# MCU.net
KiCad netlist of a schematic drawn in Altium Designer
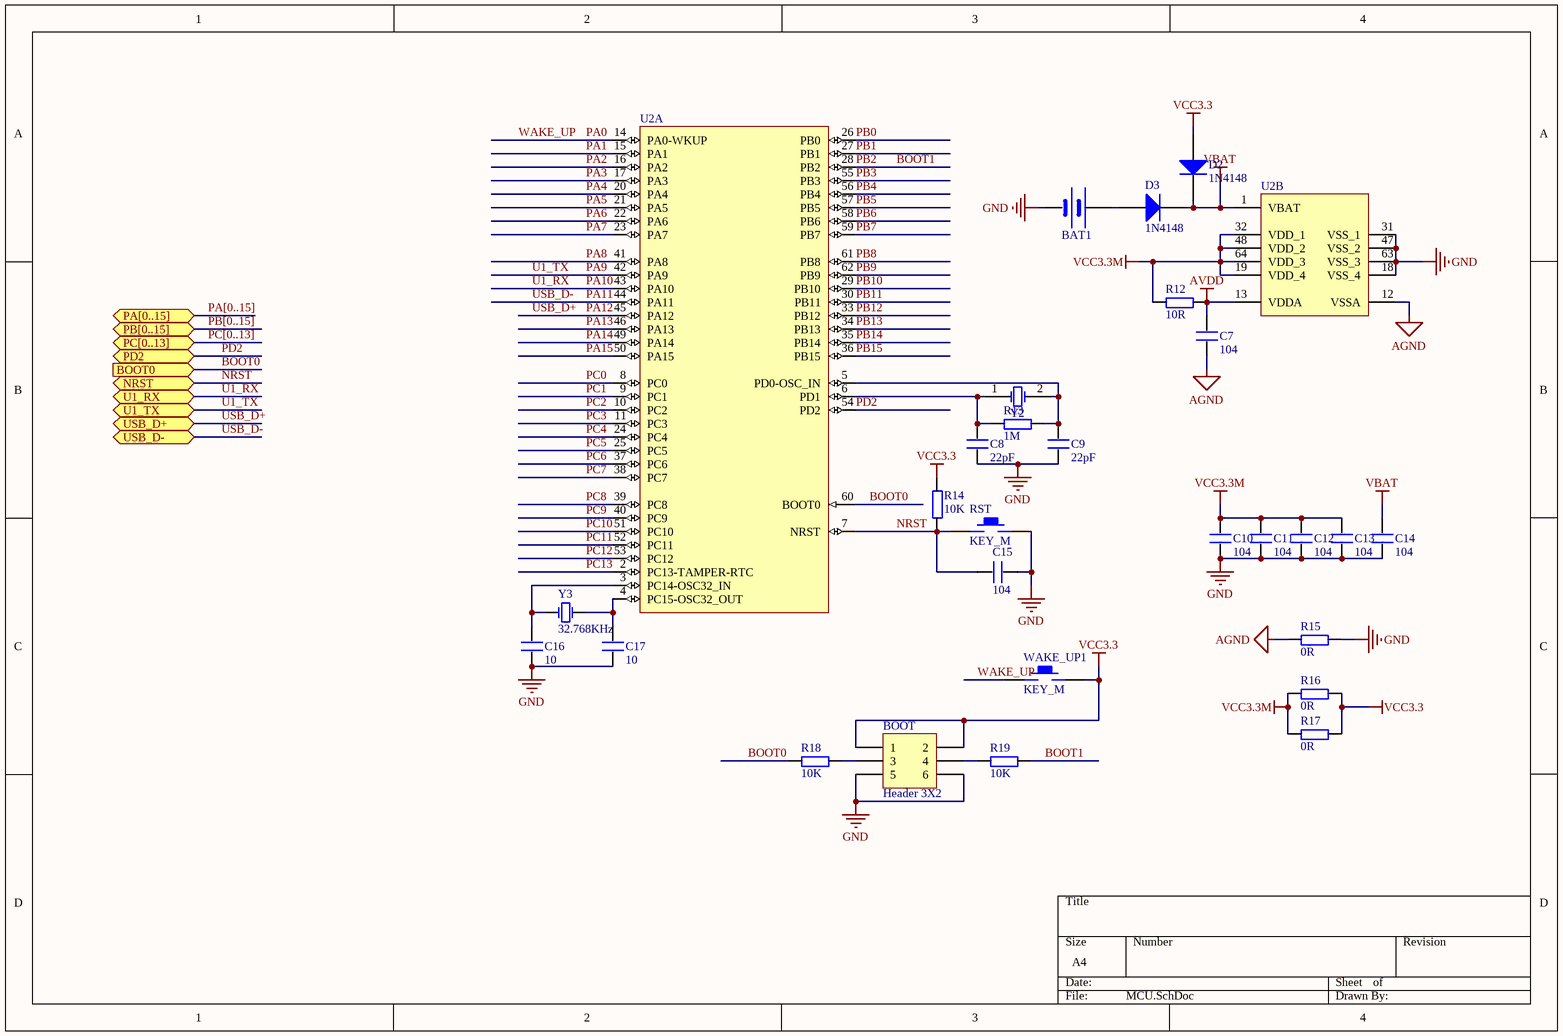
[diagram p0: MCU.SchDoc]

(export (version "E")
  (design (tool "Eeschema 10.0.6"))
  (components
    (comp (ref "BAT1")
      (value "BATT")
      (footprint "CR1220_B")
      (libsource (lib "WarShip V3 STM32103封装库") (part "BAT"))
    )
    (comp (ref "BOOT")
      (value "Header 3X2")
      (footprint "HDR2X3")
      (description "Header, 3-Pin, Dual row")
      (fields (field (name "PUBLISHER") "Altium Limited"))
      (libsource (lib "Miscellaneous Connectors") (part "Header 3X2"))
    )
    (comp (ref "C7") (value "104") (footprint "0603C") (libsource (lib "WarShip V3 STM32103封装库") (part "C")))
    (comp (ref "C8") (value "22pF") (footprint "0603C") (libsource (lib "WarShip V3 STM32103封装库") (part "C")))
    (comp (ref "C9") (value "22pF") (footprint "0603C") (libsource (lib "WarShip V3 STM32103封装库") (part "C")))
    (comp (ref "C10") (value "104") (footprint "0603C") (libsource (lib "WarShip V3 STM32103封装库") (part "C")))
    (comp (ref "C11") (value "104") (footprint "0603C") (libsource (lib "WarShip V3 STM32103封装库") (part "C")))
    (comp (ref "C12") (value "104") (footprint "0603C") (libsource (lib "WarShip V3 STM32103封装库") (part "C")))
    (comp (ref "C13") (value "104") (footprint "0603C") (libsource (lib "WarShip V3 STM32103封装库") (part "C")))
    (comp (ref "C14") (value "104") (footprint "0603C") (libsource (lib "WarShip V3 STM32103封装库") (part "C")))
    (comp (ref "C15") (value "104") (footprint "0603C") (libsource (lib "STM32F429核心板封装库") (part "C")))
    (comp (ref "C16") (value "10") (footprint "0603C") (libsource (lib "WarShip V3 STM32103封装库") (part "C")))
    (comp (ref "C17") (value "10") (footprint "0603C") (libsource (lib "WarShip V3 STM32103封装库") (part "C")))
    (comp (ref "D2")
      (value "1N4148")
      (footprint "DIODE_SOP")
      (description "Default Diode")
      (fields (field (name "PUBLISHER") "Altium Limited"))
      (libsource (lib "3D库") (part "Diode"))
    )
    (comp (ref "D3")
      (value "1N4148")
      (footprint "DIODE_SOP")
      (description "Default Diode")
      (fields (field (name "PUBLISHER") "Altium Limited"))
      (libsource (lib "3D库") (part "Diode"))
    )
    (comp (ref "R12") (value "10R") (footprint "0603R") (libsource (lib "WarShip V3 STM32103封装库") (part "R")))
    (comp (ref "R13") (value "1M") (footprint "0603R") (libsource (lib "Explorer STM32F407封装库") (part "R")))
    (comp (ref "R14") (value "10K") (footprint "0603R") (libsource (lib "STM32F429核心板封装库") (part "R")))
    (comp (ref "R15") (value "0R") (footprint "0603R") (libsource (lib "WarShip V3 STM32103封装库") (part "R")))
    (comp (ref "R16") (value "0R") (footprint "0603R") (libsource (lib "STM32F429核心板封装库") (part "R")))
    (comp (ref "R17") (value "0R") (footprint "0603R") (libsource (lib "STM32F429核心板封装库") (part "R")))
    (comp (ref "R18") (value "10K") (footprint "0603R") (libsource (lib "Explorer STM32F407封装库") (part "R")))
    (comp (ref "R19") (value "10K") (footprint "0603R") (libsource (lib "Explorer STM32F407封装库") (part "R")))
    (comp (ref "RST")
      (value "KEY_M")
      (footprint "KEY_SOP3625_B")
      (libsource (lib "STM32F429核心板封装库") (part "KEY_M"))
    )
    (comp (ref "U2")
      (value "~")
      (footprint "LQFP64-10x10mm")
      (libsource (lib "STMicroelectronics STM32 F1") (part "STM32F103RCT6"))
    )
    (comp (ref "WAKE_UP1")
      (value "KEY_M")
      (footprint "KEY_SOP3625_B")
      (libsource (lib "STM32F429核心板封装库") (part "KEY_M"))
    )
    (comp (ref "Y2")
      (value "NX3225GD-8.000M-EXS00A-CG04874[N/A]")
      (footprint "XTAL_SMD")
      (description "Crystal Oscillator")
      (fields (field (name "PUBLISHER") "Altium Limited"))
      (libsource (lib "3D库") (part "XTAL"))
    )
    (comp (ref "Y3")
      (value "32.768KHz")
      (footprint "XTAL_2SM_3R2X1R5")
      (description "普通晶振")
      (fields (field (name "PUBLISHER") "Altium Limited"))
      (libsource (lib "STM32F429核心板封装库") (part "XTAL"))
    )
  )
  (nets
    (net (code "1") (name "/BOOT0") (class "Default")
      (node (ref "R18") (pin "1") (pintype "passive"))
      (node (ref "U2") (pin "60") (pinfunction "BOOT0_60") (pintype "input"))
    )
    (net (code "2") (name "/NRST") (class "Default")
      (node (ref "C15") (pin "1") (pintype "passive"))
      (node (ref "R14") (pin "1") (pintype "passive"))
      (node (ref "RST") (pin "1") (pinfunction "1_1") (pintype "passive"))
      (node (ref "U2") (pin "7") (pinfunction "NRST_7") (pintype "bidirectional"))
    )
    (net (code "3") (name "/PA0") (class "Default")
      (node (ref "U2") (pin "14") (pinfunction "PA0-WKUP_14") (pintype "bidirectional"))
      (node (ref "WAKE_UP1") (pin "1") (pinfunction "1_1") (pintype "passive"))
    )
    (net (code "4") (name "/PA1") (class "Default")
      (node (ref "U2") (pin "15") (pinfunction "PA1_15") (pintype "bidirectional"))
    )
    (net (code "5") (name "/PA2") (class "Default")
      (node (ref "U2") (pin "16") (pinfunction "PA2_16") (pintype "bidirectional"))
    )
    (net (code "6") (name "/PA3") (class "Default")
      (node (ref "U2") (pin "17") (pinfunction "PA3_17") (pintype "bidirectional"))
    )
    (net (code "7") (name "/PA4") (class "Default")
      (node (ref "U2") (pin "20") (pinfunction "PA4_20") (pintype "bidirectional"))
    )
    (net (code "8") (name "/PA5") (class "Default")
      (node (ref "U2") (pin "21") (pinfunction "PA5_21") (pintype "bidirectional"))
    )
    (net (code "9") (name "/PA6") (class "Default")
      (node (ref "U2") (pin "22") (pinfunction "PA6_22") (pintype "bidirectional"))
    )
    (net (code "10") (name "/PA7") (class "Default")
      (node (ref "U2") (pin "23") (pinfunction "PA7_23") (pintype "bidirectional"))
    )
    (net (code "11") (name "/PA8") (class "Default")
      (node (ref "U2") (pin "41") (pinfunction "PA8_41") (pintype "bidirectional"))
    )
    (net (code "12") (name "/PA9") (class "Default")
      (node (ref "U2") (pin "42") (pinfunction "PA9_42") (pintype "bidirectional"))
    )
    (net (code "13") (name "/PA10") (class "Default")
      (node (ref "U2") (pin "43") (pinfunction "PA10_43") (pintype "bidirectional"))
    )
    (net (code "14") (name "/PA11") (class "Default")
      (node (ref "U2") (pin "44") (pinfunction "PA11_44") (pintype "bidirectional"))
    )
    (net (code "15") (name "/PA12") (class "Default")
      (node (ref "U2") (pin "45") (pinfunction "PA12_45") (pintype "bidirectional"))
    )
    (net (code "16") (name "/PA13") (class "Default")
      (node (ref "U2") (pin "46") (pinfunction "PA13_46") (pintype "bidirectional"))
    )
    (net (code "17") (name "/PA14") (class "Default")
      (node (ref "U2") (pin "49") (pinfunction "PA14_49") (pintype "bidirectional"))
    )
    (net (code "18") (name "/PA15") (class "Default")
      (node (ref "U2") (pin "50") (pinfunction "PA15_50") (pintype "bidirectional"))
    )
    (net (code "20") (name "/PB0") (class "Default")
      (node (ref "U2") (pin "26") (pinfunction "PB0_26") (pintype "bidirectional"))
    )
    (net (code "21") (name "/PB1") (class "Default")
      (node (ref "U2") (pin "27") (pinfunction "PB1_27") (pintype "bidirectional"))
    )
    (net (code "22") (name "/PB2") (class "Default")
      (node (ref "R19") (pin "2") (pintype "passive"))
      (node (ref "U2") (pin "28") (pinfunction "PB2_28") (pintype "bidirectional"))
    )
    (net (code "23") (name "/PB3") (class "Default")
      (node (ref "U2") (pin "55") (pinfunction "PB3_55") (pintype "bidirectional"))
    )
    (net (code "24") (name "/PB4") (class "Default")
      (node (ref "U2") (pin "56") (pinfunction "PB4_56") (pintype "bidirectional"))
    )
    (net (code "25") (name "/PB5") (class "Default")
      (node (ref "U2") (pin "57") (pinfunction "PB5_57") (pintype "bidirectional"))
    )
    (net (code "26") (name "/PB6") (class "Default")
      (node (ref "U2") (pin "58") (pinfunction "PB6_58") (pintype "bidirectional"))
    )
    (net (code "27") (name "/PB7") (class "Default")
      (node (ref "U2") (pin "59") (pinfunction "PB7_59") (pintype "bidirectional"))
    )
    (net (code "28") (name "/PB8") (class "Default")
      (node (ref "U2") (pin "61") (pinfunction "PB8_61") (pintype "bidirectional"))
    )
    (net (code "29") (name "/PB9") (class "Default")
      (node (ref "U2") (pin "62") (pinfunction "PB9_62") (pintype "bidirectional"))
    )
    (net (code "30") (name "/PB10") (class "Default")
      (node (ref "U2") (pin "29") (pinfunction "PB10_29") (pintype "bidirectional"))
    )
    (net (code "31") (name "/PB11") (class "Default")
      (node (ref "U2") (pin "30") (pinfunction "PB11_30") (pintype "bidirectional"))
    )
    (net (code "32") (name "/PB12") (class "Default")
      (node (ref "U2") (pin "33") (pinfunction "PB12_33") (pintype "bidirectional"))
    )
    (net (code "33") (name "/PB13") (class "Default")
      (node (ref "U2") (pin "34") (pinfunction "PB13_34") (pintype "bidirectional"))
    )
    (net (code "34") (name "/PB14") (class "Default")
      (node (ref "U2") (pin "35") (pinfunction "PB14_35") (pintype "bidirectional"))
    )
    (net (code "35") (name "/PB15") (class "Default")
      (node (ref "U2") (pin "36") (pinfunction "PB15_36") (pintype "bidirectional"))
    )
    (net (code "37") (name "/PC0") (class "Default")
      (node (ref "U2") (pin "8") (pinfunction "PC0_8") (pintype "bidirectional"))
    )
    (net (code "38") (name "/PC1") (class "Default")
      (node (ref "U2") (pin "9") (pinfunction "PC1_9") (pintype "bidirectional"))
    )
    (net (code "39") (name "/PC2") (class "Default")
      (node (ref "U2") (pin "10") (pinfunction "PC2_10") (pintype "bidirectional"))
    )
    (net (code "40") (name "/PC3") (class "Default")
      (node (ref "U2") (pin "11") (pinfunction "PC3_11") (pintype "bidirectional"))
    )
    (net (code "41") (name "/PC4") (class "Default")
      (node (ref "U2") (pin "24") (pinfunction "PC4_24") (pintype "bidirectional"))
    )
    (net (code "42") (name "/PC5") (class "Default")
      (node (ref "U2") (pin "25") (pinfunction "PC5_25") (pintype "bidirectional"))
    )
    (net (code "43") (name "/PC6") (class "Default")
      (node (ref "U2") (pin "37") (pinfunction "PC6_37") (pintype "bidirectional"))
    )
    (net (code "44") (name "/PC7") (class "Default")
      (node (ref "U2") (pin "38") (pinfunction "PC7_38") (pintype "bidirectional"))
    )
    (net (code "45") (name "/PC8") (class "Default")
      (node (ref "U2") (pin "39") (pinfunction "PC8_39") (pintype "bidirectional"))
    )
    (net (code "46") (name "/PC9") (class "Default")
      (node (ref "U2") (pin "40") (pinfunction "PC9_40") (pintype "bidirectional"))
    )
    (net (code "47") (name "/PC10") (class "Default")
      (node (ref "U2") (pin "51") (pinfunction "PC10_51") (pintype "bidirectional"))
    )
    (net (code "48") (name "/PC11") (class "Default")
      (node (ref "U2") (pin "52") (pinfunction "PC11_52") (pintype "bidirectional"))
    )
    (net (code "49") (name "/PC12") (class "Default")
      (node (ref "U2") (pin "53") (pinfunction "PC12_53") (pintype "bidirectional"))
    )
    (net (code "50") (name "/PC13") (class "Default")
      (node (ref "U2") (pin "2") (pinfunction "PC13-TAMPER-RTC_2") (pintype "bidirectional"))
    )
    (net (code "52") (name "/PD2") (class "Default")
      (node (ref "U2") (pin "54") (pinfunction "PD2_54") (pintype "bidirectional"))
    )
    (net (code "53") (name "AGND") (class "Default")
      (node (ref "C7") (pin "1") (pintype "passive"))
      (node (ref "R15") (pin "1") (pintype "passive"))
      (node (ref "U2") (pin "12") (pinfunction "VSSA_12") (pintype "power_in"))
    )
    (net (code "54") (name "AVDD") (class "Default")
      (node (ref "C7") (pin "2") (pintype "passive"))
      (node (ref "R12") (pin "2") (pintype "passive"))
      (node (ref "U2") (pin "13") (pinfunction "VDDA_13") (pintype "power_in"))
    )
    (net (code "55") (name "GND") (class "Default")
      (node (ref "BAT1") (pin "2") (pinfunction "GND_2") (pintype "passive"))
      (node (ref "BOOT") (pin "5") (pinfunction "5_5") (pintype "passive"))
      (node (ref "BOOT") (pin "6") (pinfunction "6_6") (pintype "passive"))
      (node (ref "C10") (pin "1") (pintype "passive"))
      (node (ref "C11") (pin "1") (pintype "passive"))
      (node (ref "C12") (pin "1") (pintype "passive"))
      (node (ref "C13") (pin "1") (pintype "passive"))
      (node (ref "C14") (pin "1") (pintype "passive"))
      (node (ref "C15") (pin "2") (pintype "passive"))
      (node (ref "C16") (pin "1") (pintype "passive"))
      (node (ref "C17") (pin "1") (pintype "passive"))
      (node (ref "C8") (pin "1") (pintype "passive"))
      (node (ref "C9") (pin "1") (pintype "passive"))
      (node (ref "R15") (pin "2") (pintype "passive"))
      (node (ref "RST") (pin "2") (pinfunction "2_2") (pintype "passive"))
      (node (ref "U2") (pin "18") (pinfunction "VSS_4_18") (pintype "power_in"))
      (node (ref "U2") (pin "31") (pinfunction "VSS_1_31") (pintype "power_in"))
      (node (ref "U2") (pin "47") (pinfunction "VSS_2_47") (pintype "power_in"))
      (node (ref "U2") (pin "63") (pinfunction "VSS_3_63") (pintype "power_in"))
    )
    (net (code "56") (name "Net-(BAT1-VCC)") (class "Default")
      (node (ref "BAT1") (pin "1") (pinfunction "VCC_1") (pintype "passive"))
      (node (ref "D3") (pin "1") (pinfunction "A_1") (pintype "passive"))
    )
    (net (code "57") (name "Net-(BOOT-Pad3)") (class "Default")
      (node (ref "BOOT") (pin "3") (pinfunction "3_3") (pintype "passive"))
      (node (ref "R18") (pin "2") (pintype "passive"))
    )
    (net (code "58") (name "Net-(BOOT-Pad4)") (class "Default")
      (node (ref "BOOT") (pin "4") (pinfunction "4_4") (pintype "passive"))
      (node (ref "R19") (pin "1") (pintype "passive"))
    )
    (net (code "59") (name "Net-(U2A-PC14-OSC32_IN)") (class "Default")
      (node (ref "C16") (pin "2") (pintype "passive"))
      (node (ref "U2") (pin "3") (pinfunction "PC14-OSC32_IN_3") (pintype "bidirectional"))
      (node (ref "Y3") (pin "1") (pinfunction "OSC1_1") (pintype "passive"))
    )
    (net (code "60") (name "Net-(U2A-PC15-OSC32_OUT)") (class "Default")
      (node (ref "C17") (pin "2") (pintype "passive"))
      (node (ref "U2") (pin "4") (pinfunction "PC15-OSC32_OUT_4") (pintype "bidirectional"))
      (node (ref "Y3") (pin "2") (pinfunction "OSC2_2") (pintype "passive"))
    )
    (net (code "61") (name "Net-(U2A-PD0-OSC_IN)") (class "Default")
      (node (ref "C9") (pin "2") (pintype "passive"))
      (node (ref "R13") (pin "2") (pintype "passive"))
      (node (ref "U2") (pin "5") (pinfunction "PD0-OSC_IN_5") (pintype "bidirectional"))
      (node (ref "Y2") (pin "2") (pinfunction "OSC2_2") (pintype "passive"))
    )
    (net (code "62") (name "Net-(U2A-PD1)") (class "Default")
      (node (ref "C8") (pin "2") (pintype "passive"))
      (node (ref "R13") (pin "1") (pintype "passive"))
      (node (ref "U2") (pin "6") (pinfunction "PD1_6") (pintype "bidirectional"))
      (node (ref "Y2") (pin "1") (pinfunction "OSC1_1") (pintype "passive"))
    )
    (net (code "63") (name "VBAT") (class "Default")
      (node (ref "C14") (pin "2") (pintype "passive"))
      (node (ref "D2") (pin "2") (pinfunction "K_2") (pintype "passive"))
      (node (ref "D3") (pin "2") (pinfunction "K_2") (pintype "passive"))
      (node (ref "U2") (pin "1") (pinfunction "VBAT_1") (pintype "power_in"))
    )
    (net (code "64") (name "VCC3.3") (class "Default")
      (node (ref "BOOT") (pin "1") (pinfunction "1_1") (pintype "passive"))
      (node (ref "BOOT") (pin "2") (pinfunction "2_2") (pintype "passive"))
      (node (ref "D2") (pin "1") (pinfunction "A_1") (pintype "passive"))
      (node (ref "R14") (pin "2") (pintype "passive"))
      (node (ref "R16") (pin "2") (pintype "passive"))
      (node (ref "R17") (pin "2") (pintype "passive"))
      (node (ref "WAKE_UP1") (pin "2") (pinfunction "2_2") (pintype "passive"))
    )
    (net (code "65") (name "VCC3.3M") (class "Default")
      (node (ref "C10") (pin "2") (pintype "passive"))
      (node (ref "C11") (pin "2") (pintype "passive"))
      (node (ref "C12") (pin "2") (pintype "passive"))
      (node (ref "C13") (pin "2") (pintype "passive"))
      (node (ref "R12") (pin "1") (pintype "passive"))
      (node (ref "R16") (pin "1") (pintype "passive"))
      (node (ref "R17") (pin "1") (pintype "passive"))
      (node (ref "U2") (pin "19") (pinfunction "VDD_4_19") (pintype "power_in"))
      (node (ref "U2") (pin "32") (pinfunction "VDD_1_32") (pintype "power_in"))
      (node (ref "U2") (pin "48") (pinfunction "VDD_2_48") (pintype "power_in"))
      (node (ref "U2") (pin "64") (pinfunction "VDD_3_64") (pintype "power_in"))
    )
  )
)
